# misc_sensors.net
KiCad netlist of a schematic drawn in Altium Designer
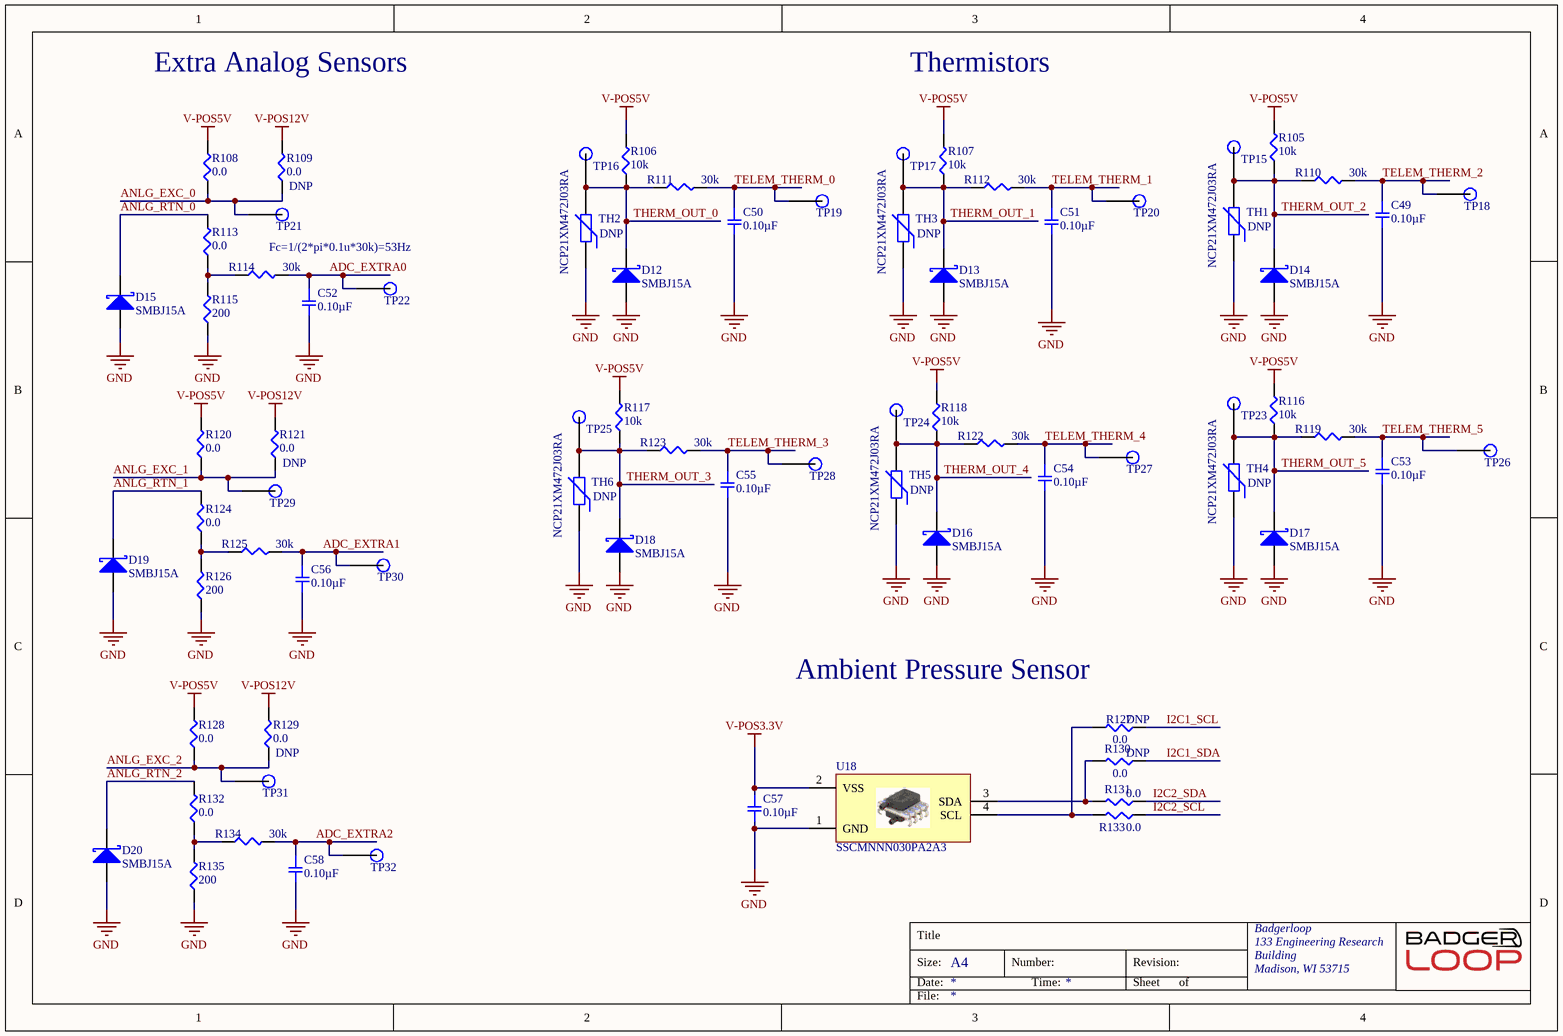
[diagram p0: misc_sensors.SchDoc]

(export (version "E")
  (design (tool "Eeschema 10.0.6"))
  (components
    (comp (ref "C49")
      (value "0.10µF")
      (footprint "SMD-0805C")
      (description "CAP CER 0.1UF 16V X7R 0805")
      (fields
        (field (name "DIGI-KEY PART NUMBER") "490-1683-1-ND")
        (field (name "PART NUMBER") "GRM219R71C104KA01D")
      )
      (libsource (lib "capacitors") (part "GRM219R71C104KA01D"))
    )
    (comp (ref "C50")
      (value "0.10µF")
      (footprint "SMD-0805C")
      (description "CAP CER 0.1UF 16V X7R 0805")
      (fields
        (field (name "DIGI-KEY PART NUMBER") "490-1683-1-ND")
        (field (name "PART NUMBER") "GRM219R71C104KA01D")
      )
      (libsource (lib "capacitors") (part "GRM219R71C104KA01D"))
    )
    (comp (ref "C51")
      (value "0.10µF")
      (footprint "SMD-0805C")
      (description "CAP CER 0.1UF 16V X7R 0805")
      (fields
        (field (name "DIGI-KEY PART NUMBER") "490-1683-1-ND")
        (field (name "PART NUMBER") "GRM219R71C104KA01D")
      )
      (libsource (lib "capacitors") (part "GRM219R71C104KA01D"))
    )
    (comp (ref "C52")
      (value "0.10µF")
      (footprint "SMD-0805C")
      (description "CAP CER 0.1UF 25V X7R 0805")
      (fields
        (field (name "DIGI-KEY PART NUMBER") "490-12754-1-ND")
        (field (name "PART NUMBER") "GRM219R71E104KA01D")
      )
      (libsource (lib "capacitors") (part "GRM219R71E104KA01D"))
    )
    (comp (ref "C53")
      (value "0.10µF")
      (footprint "SMD-0805C")
      (description "CAP CER 0.1UF 16V X7R 0805")
      (fields
        (field (name "DIGI-KEY PART NUMBER") "490-1683-1-ND")
        (field (name "PART NUMBER") "GRM219R71C104KA01D")
      )
      (libsource (lib "capacitors") (part "GRM219R71C104KA01D"))
    )
    (comp (ref "C54")
      (value "0.10µF")
      (footprint "SMD-0805C")
      (description "CAP CER 0.1UF 16V X7R 0805")
      (fields
        (field (name "DIGI-KEY PART NUMBER") "490-1683-1-ND")
        (field (name "PART NUMBER") "GRM219R71C104KA01D")
      )
      (libsource (lib "capacitors") (part "GRM219R71C104KA01D"))
    )
    (comp (ref "C55")
      (value "0.10µF")
      (footprint "SMD-0805C")
      (description "CAP CER 0.1UF 16V X7R 0805")
      (fields
        (field (name "DIGI-KEY PART NUMBER") "490-1683-1-ND")
        (field (name "PART NUMBER") "GRM219R71C104KA01D")
      )
      (libsource (lib "capacitors") (part "GRM219R71C104KA01D"))
    )
    (comp (ref "C56")
      (value "0.10µF")
      (footprint "SMD-0805C")
      (description "CAP CER 0.1UF 25V X7R 0805")
      (fields
        (field (name "DIGI-KEY PART NUMBER") "490-12754-1-ND")
        (field (name "PART NUMBER") "GRM219R71E104KA01D")
      )
      (libsource (lib "capacitors") (part "GRM219R71E104KA01D"))
    )
    (comp (ref "C57")
      (value "0.10µF")
      (footprint "SMD-0805C")
      (description "CAP CER 0.1UF 25V X7R 0805")
      (fields
        (field (name "DIGI-KEY PART NUMBER") "490-12754-1-ND")
        (field (name "PART NUMBER") "GRM219R71E104KA01D")
      )
      (libsource (lib "capacitors") (part "GRM219R71E104KA01D"))
    )
    (comp (ref "C58")
      (value "0.10µF")
      (footprint "SMD-0805C")
      (description "CAP CER 0.1UF 25V X7R 0805")
      (fields
        (field (name "DIGI-KEY PART NUMBER") "490-12754-1-ND")
        (field (name "PART NUMBER") "GRM219R71E104KA01D")
      )
      (libsource (lib "capacitors") (part "GRM219R71E104KA01D"))
    )
    (comp (ref "D12")
      (value "SMBJ15A")
      (footprint "DIOM4436X26N")
      (description "TVS DIODE 15V 24.4V DO214AA")
      (fields (field (name "MANUFACTURER") "Littelfuse") (field (name "VOLTAGE") "5V"))
      (libsource (lib "misc") (part "SMBJ15A"))
    )
    (comp (ref "D13")
      (value "SMBJ15A")
      (footprint "DIOM4436X26N")
      (description "TVS DIODE 15V 24.4V DO214AA")
      (fields (field (name "MANUFACTURER") "Littelfuse") (field (name "VOLTAGE") "5V"))
      (libsource (lib "misc") (part "SMBJ15A"))
    )
    (comp (ref "D14")
      (value "SMBJ15A")
      (footprint "DIOM4436X26N")
      (description "TVS DIODE 15V 24.4V DO214AA")
      (fields (field (name "MANUFACTURER") "Littelfuse") (field (name "VOLTAGE") "5V"))
      (libsource (lib "misc") (part "SMBJ15A"))
    )
    (comp (ref "D15")
      (value "SMBJ15A")
      (footprint "DIOM4436X26N")
      (description "TVS DIODE 15V 24.4V DO214AA")
      (fields (field (name "MANUFACTURER") "Littelfuse") (field (name "VOLTAGE") "5V"))
      (libsource (lib "misc") (part "SMBJ15A"))
    )
    (comp (ref "D16")
      (value "SMBJ15A")
      (footprint "DIOM4436X26N")
      (description "TVS DIODE 15V 24.4V DO214AA")
      (fields (field (name "MANUFACTURER") "Littelfuse") (field (name "VOLTAGE") "5V"))
      (libsource (lib "misc") (part "SMBJ15A"))
    )
    (comp (ref "D17")
      (value "SMBJ15A")
      (footprint "DIOM4436X26N")
      (description "TVS DIODE 15V 24.4V DO214AA")
      (fields (field (name "MANUFACTURER") "Littelfuse") (field (name "VOLTAGE") "5V"))
      (libsource (lib "misc") (part "SMBJ15A"))
    )
    (comp (ref "D18")
      (value "SMBJ15A")
      (footprint "DIOM4436X26N")
      (description "TVS DIODE 15V 24.4V DO214AA")
      (fields (field (name "MANUFACTURER") "Littelfuse") (field (name "VOLTAGE") "5V"))
      (libsource (lib "misc") (part "SMBJ15A"))
    )
    (comp (ref "D19")
      (value "SMBJ15A")
      (footprint "DIOM4436X26N")
      (description "TVS DIODE 15V 24.4V DO214AA")
      (fields (field (name "MANUFACTURER") "Littelfuse") (field (name "VOLTAGE") "5V"))
      (libsource (lib "misc") (part "SMBJ15A"))
    )
    (comp (ref "D20")
      (value "SMBJ15A")
      (footprint "DIOM4436X26N")
      (description "TVS DIODE 15V 24.4V DO214AA")
      (fields (field (name "MANUFACTURER") "Littelfuse") (field (name "VOLTAGE") "5V"))
      (libsource (lib "misc") (part "SMBJ15A"))
    )
    (comp (ref "R105")
      (value "10k")
      (footprint "SMD-0805-RES")
      (description "RES SMD 10K OHM 1% 1/2W 0805")
      (fields
        (field (name "PART NUMBER") "ERJ-P06F1002V")
        (field (name "DIGI-KEY PART NUMBER") "P16059CT-ND")
      )
      (libsource (lib "resistors") (part "ERJ-P06F1002V"))
    )
    (comp (ref "R106")
      (value "10k")
      (footprint "SMD-0805-RES")
      (description "RES SMD 10K OHM 1% 1/2W 0805")
      (fields
        (field (name "PART NUMBER") "ERJ-P06F1002V")
        (field (name "DIGI-KEY PART NUMBER") "P16059CT-ND")
      )
      (libsource (lib "resistors") (part "ERJ-P06F1002V"))
    )
    (comp (ref "R107")
      (value "10k")
      (footprint "SMD-0805-RES")
      (description "RES SMD 10K OHM 1% 1/2W 0805")
      (fields
        (field (name "PART NUMBER") "ERJ-P06F1002V")
        (field (name "DIGI-KEY PART NUMBER") "P16059CT-ND")
      )
      (libsource (lib "resistors") (part "ERJ-P06F1002V"))
    )
    (comp (ref "R108")
      (value "0.0")
      (footprint "SMD-0805-RES")
      (description "RES SMD 0.0 OHM JUMPER 1/8W 0805")
      (fields (field (name "PART NUMBER") "ERJ-6GEY0R00V") (field (name "DIGI-KEY PART NUMBER") "P0.0ACT-ND"))
      (libsource (lib "resistors") (part "ERJ-6GEY0R00V"))
    )
    (comp (ref "R109")
      (value "0.0")
      (footprint "SMD-0805-RES")
      (description "RES SMD 0.0 OHM JUMPER 1/8W 0805")
      (fields
        (field (name "PART NUMBER") "ERJ-6GEY0R00V")
        (field (name "DIGI-KEY PART NUMBER") "P0.0ACT-ND")
        (field (name "DNP") "DNP")
      )
      (libsource (lib "resistors") (part "ERJ-6GEY0R00V"))
    )
    (comp (ref "R110")
      (value "30k")
      (footprint "SMD-0805-RES")
      (description "RES SMD 30K OHM 1% 1/8W 0805")
      (fields
        (field (name "PART NUMBER") "ERJ-6ENF3002V")
        (field (name "DIGI-KEY PART NUMBER") "P30.0KCCT-ND")
      )
      (libsource (lib "resistors") (part "ERJ-6ENF3002V"))
    )
    (comp (ref "R111")
      (value "30k")
      (footprint "SMD-0805-RES")
      (description "RES SMD 30K OHM 1% 1/8W 0805")
      (fields
        (field (name "PART NUMBER") "ERJ-6ENF3002V")
        (field (name "DIGI-KEY PART NUMBER") "P30.0KCCT-ND")
      )
      (libsource (lib "resistors") (part "ERJ-6ENF3002V"))
    )
    (comp (ref "R112")
      (value "30k")
      (footprint "SMD-0805-RES")
      (description "RES SMD 30K OHM 1% 1/8W 0805")
      (fields
        (field (name "PART NUMBER") "ERJ-6ENF3002V")
        (field (name "DIGI-KEY PART NUMBER") "P30.0KCCT-ND")
      )
      (libsource (lib "resistors") (part "ERJ-6ENF3002V"))
    )
    (comp (ref "R113")
      (value "0.0")
      (footprint "SMD-0805-RES")
      (description "RES SMD 0.0 OHM JUMPER 1/8W 0805")
      (fields (field (name "PART NUMBER") "ERJ-6GEY0R00V") (field (name "DIGI-KEY PART NUMBER") "P0.0ACT-ND"))
      (libsource (lib "resistors") (part "ERJ-6GEY0R00V"))
    )
    (comp (ref "R114")
      (value "30k")
      (footprint "SMD-0805-RES")
      (description "RES SMD 30K OHM 1% 1/8W 0805")
      (fields
        (field (name "PART NUMBER") "ERJ-6ENF3002V")
        (field (name "DIGI-KEY PART NUMBER") "P30.0KCCT-ND")
      )
      (libsource (lib "resistors") (part "ERJ-6ENF3002V"))
    )
    (comp (ref "R115")
      (value "200")
      (footprint "SMD-0805-RES")
      (description "RES SMD 200 OHM 1% 1/2W 0805")
      (fields
        (field (name "PART NUMBER") "ERJ-P06F2000V")
        (field (name "DIGI-KEY PART NUMBER") "P16064CT-ND")
      )
      (libsource (lib "resistors") (part "ERJ-P06F2000V"))
    )
    (comp (ref "R116")
      (value "10k")
      (footprint "SMD-0805-RES")
      (description "RES SMD 10K OHM 1% 1/2W 0805")
      (fields
        (field (name "PART NUMBER") "ERJ-P06F1002V")
        (field (name "DIGI-KEY PART NUMBER") "P16059CT-ND")
      )
      (libsource (lib "resistors") (part "ERJ-P06F1002V"))
    )
    (comp (ref "R117")
      (value "10k")
      (footprint "SMD-0805-RES")
      (description "RES SMD 10K OHM 1% 1/2W 0805")
      (fields
        (field (name "PART NUMBER") "ERJ-P06F1002V")
        (field (name "DIGI-KEY PART NUMBER") "P16059CT-ND")
      )
      (libsource (lib "resistors") (part "ERJ-P06F1002V"))
    )
    (comp (ref "R118")
      (value "10k")
      (footprint "SMD-0805-RES")
      (description "RES SMD 10K OHM 1% 1/2W 0805")
      (fields
        (field (name "PART NUMBER") "ERJ-P06F1002V")
        (field (name "DIGI-KEY PART NUMBER") "P16059CT-ND")
      )
      (libsource (lib "resistors") (part "ERJ-P06F1002V"))
    )
    (comp (ref "R119")
      (value "30k")
      (footprint "SMD-0805-RES")
      (description "RES SMD 30K OHM 1% 1/8W 0805")
      (fields
        (field (name "PART NUMBER") "ERJ-6ENF3002V")
        (field (name "DIGI-KEY PART NUMBER") "P30.0KCCT-ND")
      )
      (libsource (lib "resistors") (part "ERJ-6ENF3002V"))
    )
    (comp (ref "R120")
      (value "0.0")
      (footprint "SMD-0805-RES")
      (description "RES SMD 0.0 OHM JUMPER 1/8W 0805")
      (fields (field (name "PART NUMBER") "ERJ-6GEY0R00V") (field (name "DIGI-KEY PART NUMBER") "P0.0ACT-ND"))
      (libsource (lib "resistors") (part "ERJ-6GEY0R00V"))
    )
    (comp (ref "R121")
      (value "0.0")
      (footprint "SMD-0805-RES")
      (description "RES SMD 0.0 OHM JUMPER 1/8W 0805")
      (fields
        (field (name "PART NUMBER") "ERJ-6GEY0R00V")
        (field (name "DIGI-KEY PART NUMBER") "P0.0ACT-ND")
        (field (name "DNP") "DNP")
      )
      (libsource (lib "resistors") (part "ERJ-6GEY0R00V"))
    )
    (comp (ref "R122")
      (value "30k")
      (footprint "SMD-0805-RES")
      (description "RES SMD 30K OHM 1% 1/8W 0805")
      (fields
        (field (name "PART NUMBER") "ERJ-6ENF3002V")
        (field (name "DIGI-KEY PART NUMBER") "P30.0KCCT-ND")
      )
      (libsource (lib "resistors") (part "ERJ-6ENF3002V"))
    )
    (comp (ref "R123")
      (value "30k")
      (footprint "SMD-0805-RES")
      (description "RES SMD 30K OHM 1% 1/8W 0805")
      (fields
        (field (name "PART NUMBER") "ERJ-6ENF3002V")
        (field (name "DIGI-KEY PART NUMBER") "P30.0KCCT-ND")
      )
      (libsource (lib "resistors") (part "ERJ-6ENF3002V"))
    )
    (comp (ref "R124")
      (value "0.0")
      (footprint "SMD-0805-RES")
      (description "RES SMD 0.0 OHM JUMPER 1/8W 0805")
      (fields (field (name "PART NUMBER") "ERJ-6GEY0R00V") (field (name "DIGI-KEY PART NUMBER") "P0.0ACT-ND"))
      (libsource (lib "resistors") (part "ERJ-6GEY0R00V"))
    )
    (comp (ref "R125")
      (value "30k")
      (footprint "SMD-0805-RES")
      (description "RES SMD 30K OHM 1% 1/8W 0805")
      (fields
        (field (name "PART NUMBER") "ERJ-6ENF3002V")
        (field (name "DIGI-KEY PART NUMBER") "P30.0KCCT-ND")
      )
      (libsource (lib "resistors") (part "ERJ-6ENF3002V"))
    )
    (comp (ref "R126")
      (value "200")
      (footprint "SMD-0805-RES")
      (description "RES SMD 200 OHM 1% 1/2W 0805")
      (fields
        (field (name "PART NUMBER") "ERJ-P06F2000V")
        (field (name "DIGI-KEY PART NUMBER") "P16064CT-ND")
      )
      (libsource (lib "resistors") (part "ERJ-P06F2000V"))
    )
    (comp (ref "R127")
      (value "0.0")
      (footprint "SMD-0805-RES")
      (description "RES SMD 0.0 OHM JUMPER 1/8W 0805")
      (fields
        (field (name "PART NUMBER") "ERJ-6GEY0R00V")
        (field (name "DIGI-KEY PART NUMBER") "P0.0ACT-ND")
        (field (name "DNP") "DNP")
      )
      (libsource (lib "resistors") (part "ERJ-6GEY0R00V"))
    )
    (comp (ref "R128")
      (value "0.0")
      (footprint "SMD-0805-RES")
      (description "RES SMD 0.0 OHM JUMPER 1/8W 0805")
      (fields (field (name "PART NUMBER") "ERJ-6GEY0R00V") (field (name "DIGI-KEY PART NUMBER") "P0.0ACT-ND"))
      (libsource (lib "resistors") (part "ERJ-6GEY0R00V"))
    )
    (comp (ref "R129")
      (value "0.0")
      (footprint "SMD-0805-RES")
      (description "RES SMD 0.0 OHM JUMPER 1/8W 0805")
      (fields
        (field (name "PART NUMBER") "ERJ-6GEY0R00V")
        (field (name "DIGI-KEY PART NUMBER") "P0.0ACT-ND")
        (field (name "DNP") "DNP")
      )
      (libsource (lib "resistors") (part "ERJ-6GEY0R00V"))
    )
    (comp (ref "R130")
      (value "0.0")
      (footprint "SMD-0805-RES")
      (description "RES SMD 0.0 OHM JUMPER 1/8W 0805")
      (fields
        (field (name "PART NUMBER") "ERJ-6GEY0R00V")
        (field (name "DIGI-KEY PART NUMBER") "P0.0ACT-ND")
        (field (name "DNP") "DNP")
      )
      (libsource (lib "resistors") (part "ERJ-6GEY0R00V"))
    )
    (comp (ref "R131")
      (value "0.0")
      (footprint "SMD-0805-RES")
      (description "RES SMD 0.0 OHM JUMPER 1/8W 0805")
      (fields (field (name "PART NUMBER") "ERJ-6GEY0R00V") (field (name "DIGI-KEY PART NUMBER") "P0.0ACT-ND"))
      (libsource (lib "resistors") (part "ERJ-6GEY0R00V"))
    )
    (comp (ref "R132")
      (value "0.0")
      (footprint "SMD-0805-RES")
      (description "RES SMD 0.0 OHM JUMPER 1/8W 0805")
      (fields (field (name "PART NUMBER") "ERJ-6GEY0R00V") (field (name "DIGI-KEY PART NUMBER") "P0.0ACT-ND"))
      (libsource (lib "resistors") (part "ERJ-6GEY0R00V"))
    )
    (comp (ref "R133")
      (value "0.0")
      (footprint "SMD-0805-RES")
      (description "RES SMD 0.0 OHM JUMPER 1/8W 0805")
      (fields (field (name "PART NUMBER") "ERJ-6GEY0R00V") (field (name "DIGI-KEY PART NUMBER") "P0.0ACT-ND"))
      (libsource (lib "resistors") (part "ERJ-6GEY0R00V"))
    )
    (comp (ref "R134")
      (value "30k")
      (footprint "SMD-0805-RES")
      (description "RES SMD 30K OHM 1% 1/8W 0805")
      (fields
        (field (name "PART NUMBER") "ERJ-6ENF3002V")
        (field (name "DIGI-KEY PART NUMBER") "P30.0KCCT-ND")
      )
      (libsource (lib "resistors") (part "ERJ-6ENF3002V"))
    )
    (comp (ref "R135")
      (value "200")
      (footprint "SMD-0805-RES")
      (description "RES SMD 200 OHM 1% 1/2W 0805")
      (fields
        (field (name "PART NUMBER") "ERJ-P06F2000V")
        (field (name "DIGI-KEY PART NUMBER") "P16064CT-ND")
      )
      (libsource (lib "resistors") (part "ERJ-P06F2000V"))
    )
    (comp (ref "TH1")
      (value "NCP21XM472J03RA")
      (footprint "SMD-0805-RES")
      (description "NTC THERMISTOR 4.7K OHM 5% 0805")
      (fields
        (field (name "MANUFACTURER") "Murata")
        (field (name "TOLERANCE") "5%")
        (field (name "DNP") "DNP")
      )
      (libsource (lib "misc") (part "NCP21XM472J03RA"))
    )
    (comp (ref "TH2")
      (value "NCP21XM472J03RA")
      (footprint "SMD-0805-RES")
      (description "NTC THERMISTOR 4.7K OHM 5% 0805")
      (fields
        (field (name "MANUFACTURER") "Murata")
        (field (name "TOLERANCE") "5%")
        (field (name "DNP") "DNP")
      )
      (libsource (lib "misc") (part "NCP21XM472J03RA"))
    )
    (comp (ref "TH3")
      (value "NCP21XM472J03RA")
      (footprint "SMD-0805-RES")
      (description "NTC THERMISTOR 4.7K OHM 5% 0805")
      (fields
        (field (name "MANUFACTURER") "Murata")
        (field (name "TOLERANCE") "5%")
        (field (name "DNP") "DNP")
      )
      (libsource (lib "misc") (part "NCP21XM472J03RA"))
    )
    (comp (ref "TH4")
      (value "NCP21XM472J03RA")
      (footprint "SMD-0805-RES")
      (description "NTC THERMISTOR 4.7K OHM 5% 0805")
      (fields
        (field (name "MANUFACTURER") "Murata")
        (field (name "TOLERANCE") "5%")
        (field (name "DNP") "DNP")
      )
      (libsource (lib "misc") (part "NCP21XM472J03RA"))
    )
    (comp (ref "TH5")
      (value "NCP21XM472J03RA")
      (footprint "SMD-0805-RES")
      (description "NTC THERMISTOR 4.7K OHM 5% 0805")
      (fields
        (field (name "MANUFACTURER") "Murata")
        (field (name "TOLERANCE") "5%")
        (field (name "DNP") "DNP")
      )
      (libsource (lib "misc") (part "NCP21XM472J03RA"))
    )
    (comp (ref "TH6")
      (value "NCP21XM472J03RA")
      (footprint "SMD-0805-RES")
      (description "NTC THERMISTOR 4.7K OHM 5% 0805")
      (fields
        (field (name "MANUFACTURER") "Murata")
        (field (name "TOLERANCE") "5%")
        (field (name "DNP") "DNP")
      )
      (libsource (lib "misc") (part "NCP21XM472J03RA"))
    )
    (comp (ref "TP15")
      (value "TP")
      (footprint "Test Point")
      (description "SMD TEST POINT")
      (libsource (lib "misc") (part "TP"))
    )
    (comp (ref "TP16")
      (value "TP")
      (footprint "Test Point")
      (description "SMD TEST POINT")
      (libsource (lib "misc") (part "TP"))
    )
    (comp (ref "TP17")
      (value "TP")
      (footprint "Test Point")
      (description "SMD TEST POINT")
      (libsource (lib "misc") (part "TP"))
    )
    (comp (ref "TP18")
      (value "TP")
      (footprint "Test Point")
      (description "SMD TEST POINT")
      (libsource (lib "misc") (part "TP"))
    )
    (comp (ref "TP19")
      (value "TP")
      (footprint "Test Point")
      (description "SMD TEST POINT")
      (libsource (lib "misc") (part "TP"))
    )
    (comp (ref "TP20")
      (value "TP")
      (footprint "Test Point")
      (description "SMD TEST POINT")
      (libsource (lib "misc") (part "TP"))
    )
    (comp (ref "TP21")
      (value "TP")
      (footprint "Test Point")
      (description "SMD TEST POINT")
      (libsource (lib "misc") (part "TP"))
    )
    (comp (ref "TP22")
      (value "TP")
      (footprint "Test Point")
      (description "SMD TEST POINT")
      (libsource (lib "misc") (part "TP"))
    )
    (comp (ref "TP23")
      (value "TP")
      (footprint "Test Point")
      (description "SMD TEST POINT")
      (libsource (lib "misc") (part "TP"))
    )
    (comp (ref "TP24")
      (value "TP")
      (footprint "Test Point")
      (description "SMD TEST POINT")
      (libsource (lib "misc") (part "TP"))
    )
    (comp (ref "TP25")
      (value "TP")
      (footprint "Test Point")
      (description "SMD TEST POINT")
      (libsource (lib "misc") (part "TP"))
    )
    (comp (ref "TP26")
      (value "TP")
      (footprint "Test Point")
      (description "SMD TEST POINT")
      (libsource (lib "misc") (part "TP"))
    )
    (comp (ref "TP27")
      (value "TP")
      (footprint "Test Point")
      (description "SMD TEST POINT")
      (libsource (lib "misc") (part "TP"))
    )
    (comp (ref "TP28")
      (value "TP")
      (footprint "Test Point")
      (description "SMD TEST POINT")
      (libsource (lib "misc") (part "TP"))
    )
    (comp (ref "TP29")
      (value "TP")
      (footprint "Test Point")
      (description "SMD TEST POINT")
      (libsource (lib "misc") (part "TP"))
    )
    (comp (ref "TP30")
      (value "TP")
      (footprint "Test Point")
      (description "SMD TEST POINT")
      (libsource (lib "misc") (part "TP"))
    )
    (comp (ref "TP31")
      (value "TP")
      (footprint "Test Point")
      (description "SMD TEST POINT")
      (libsource (lib "misc") (part "TP"))
    )
    (comp (ref "TP32")
      (value "TP")
      (footprint "Test Point")
      (description "SMD TEST POINT")
      (libsource (lib "misc") (part "TP"))
    )
    (comp (ref "U18")
      (value "SSCMNNN030PA2A3")
      (footprint "8-SMT")
      (description "Honeywell Digital Pressure Sensor")
      (libsource (lib "ic") (part "SSCMNNN030PA2A3"))
    )
  )
  (nets
    (net (code "1") (name "/ADC_EXTRA0") (class "Default")
      (node (ref "C52") (pin "1") (pinfunction "1_1") (pintype "passive"))
      (node (ref "R114") (pin "2") (pinfunction "2_2") (pintype "passive"))
      (node (ref "TP22") (pin "1") (pinfunction "1_1") (pintype "passive"))
    )
    (net (code "2") (name "/ADC_EXTRA1") (class "Default")
      (node (ref "C56") (pin "1") (pinfunction "1_1") (pintype "passive"))
      (node (ref "R125") (pin "2") (pinfunction "2_2") (pintype "passive"))
      (node (ref "TP30") (pin "1") (pinfunction "1_1") (pintype "passive"))
    )
    (net (code "3") (name "/ADC_EXTRA2") (class "Default")
      (node (ref "C58") (pin "1") (pinfunction "1_1") (pintype "passive"))
      (node (ref "R134") (pin "2") (pinfunction "2_2") (pintype "passive"))
      (node (ref "TP32") (pin "1") (pinfunction "1_1") (pintype "passive"))
    )
    (net (code "4") (name "/ANLG_EXC_0") (class "Default")
      (node (ref "R108") (pin "1") (pinfunction "1_1") (pintype "passive"))
      (node (ref "R109") (pin "1") (pinfunction "1_1") (pintype "passive"))
      (node (ref "TP21") (pin "1") (pinfunction "1_1") (pintype "passive"))
    )
    (net (code "5") (name "/ANLG_EXC_1") (class "Default")
      (node (ref "R120") (pin "1") (pinfunction "1_1") (pintype "passive"))
      (node (ref "R121") (pin "1") (pinfunction "1_1") (pintype "passive"))
      (node (ref "TP29") (pin "1") (pinfunction "1_1") (pintype "passive"))
    )
    (net (code "6") (name "/ANLG_EXC_2") (class "Default")
      (node (ref "R128") (pin "1") (pinfunction "1_1") (pintype "passive"))
      (node (ref "R129") (pin "1") (pinfunction "1_1") (pintype "passive"))
      (node (ref "TP31") (pin "1") (pinfunction "1_1") (pintype "passive"))
    )
    (net (code "7") (name "/ANLG_RTN_0") (class "Default")
      (node (ref "D15") (pin "1") (pinfunction "A_1") (pintype "passive"))
      (node (ref "R113") (pin "2") (pinfunction "2_2") (pintype "passive"))
    )
    (net (code "8") (name "/ANLG_RTN_1") (class "Default")
      (node (ref "D19") (pin "1") (pinfunction "A_1") (pintype "passive"))
      (node (ref "R124") (pin "2") (pinfunction "2_2") (pintype "passive"))
    )
    (net (code "9") (name "/ANLG_RTN_2") (class "Default")
      (node (ref "D20") (pin "1") (pinfunction "A_1") (pintype "passive"))
      (node (ref "R132") (pin "2") (pinfunction "2_2") (pintype "passive"))
    )
    (net (code "10") (name "/I2C1_SCL") (class "Default")
      (node (ref "R127") (pin "1") (pinfunction "1_1") (pintype "passive"))
    )
    (net (code "11") (name "/I2C1_SDA") (class "Default")
      (node (ref "R130") (pin "1") (pinfunction "1_1") (pintype "passive"))
    )
    (net (code "12") (name "/I2C2_SCL") (class "Default")
      (node (ref "R133") (pin "1") (pinfunction "1_1") (pintype "passive"))
    )
    (net (code "13") (name "/I2C2_SDA") (class "Default")
      (node (ref "R131") (pin "1") (pinfunction "1_1") (pintype "passive"))
    )
    (net (code "14") (name "/TELEM_THERM_0") (class "Default")
      (node (ref "C50") (pin "1") (pinfunction "1_1") (pintype "passive"))
      (node (ref "R111") (pin "2") (pinfunction "2_2") (pintype "passive"))
      (node (ref "TP19") (pin "1") (pinfunction "1_1") (pintype "passive"))
    )
    (net (code "15") (name "/TELEM_THERM_1") (class "Default")
      (node (ref "C51") (pin "1") (pinfunction "1_1") (pintype "passive"))
      (node (ref "R112") (pin "2") (pinfunction "2_2") (pintype "passive"))
      (node (ref "TP20") (pin "1") (pinfunction "1_1") (pintype "passive"))
    )
    (net (code "16") (name "/TELEM_THERM_2") (class "Default")
      (node (ref "C49") (pin "1") (pinfunction "1_1") (pintype "passive"))
      (node (ref "R110") (pin "2") (pinfunction "2_2") (pintype "passive"))
      (node (ref "TP18") (pin "1") (pinfunction "1_1") (pintype "passive"))
    )
    (net (code "17") (name "/TELEM_THERM_3") (class "Default")
      (node (ref "C55") (pin "1") (pinfunction "1_1") (pintype "passive"))
      (node (ref "R123") (pin "2") (pinfunction "2_2") (pintype "passive"))
      (node (ref "TP28") (pin "1") (pinfunction "1_1") (pintype "passive"))
    )
    (net (code "18") (name "/TELEM_THERM_4") (class "Default")
      (node (ref "C54") (pin "1") (pinfunction "1_1") (pintype "passive"))
      (node (ref "R122") (pin "2") (pinfunction "2_2") (pintype "passive"))
      (node (ref "TP27") (pin "1") (pinfunction "1_1") (pintype "passive"))
    )
    (net (code "19") (name "/TELEM_THERM_5") (class "Default")
      (node (ref "C53") (pin "1") (pinfunction "1_1") (pintype "passive"))
      (node (ref "R119") (pin "2") (pinfunction "2_2") (pintype "passive"))
      (node (ref "TP26") (pin "1") (pinfunction "1_1") (pintype "passive"))
    )
    (net (code "20") (name "/THERM_OUT_0") (class "Default")
      (node (ref "D12") (pin "1") (pinfunction "A_1") (pintype "passive"))
      (node (ref "R106") (pin "1") (pinfunction "1_1") (pintype "passive"))
      (node (ref "R111") (pin "1") (pinfunction "1_1") (pintype "passive"))
      (node (ref "TH2") (pin "2") (pinfunction "2_2") (pintype "passive"))
      (node (ref "TP16") (pin "1") (pinfunction "1_1") (pintype "passive"))
    )
    (net (code "21") (name "/THERM_OUT_1") (class "Default")
      (node (ref "D13") (pin "1") (pinfunction "A_1") (pintype "passive"))
      (node (ref "R107") (pin "1") (pinfunction "1_1") (pintype "passive"))
      (node (ref "R112") (pin "1") (pinfunction "1_1") (pintype "passive"))
      (node (ref "TH3") (pin "2") (pinfunction "2_2") (pintype "passive"))
      (node (ref "TP17") (pin "1") (pinfunction "1_1") (pintype "passive"))
    )
    (net (code "22") (name "/THERM_OUT_2") (class "Default")
      (node (ref "D14") (pin "1") (pinfunction "A_1") (pintype "passive"))
      (node (ref "R105") (pin "1") (pinfunction "1_1") (pintype "passive"))
      (node (ref "R110") (pin "1") (pinfunction "1_1") (pintype "passive"))
      (node (ref "TH1") (pin "2") (pinfunction "2_2") (pintype "passive"))
      (node (ref "TP15") (pin "1") (pinfunction "1_1") (pintype "passive"))
    )
    (net (code "23") (name "/THERM_OUT_3") (class "Default")
      (node (ref "D18") (pin "1") (pinfunction "A_1") (pintype "passive"))
      (node (ref "R117") (pin "1") (pinfunction "1_1") (pintype "passive"))
      (node (ref "R123") (pin "1") (pinfunction "1_1") (pintype "passive"))
      (node (ref "TH6") (pin "2") (pinfunction "2_2") (pintype "passive"))
      (node (ref "TP25") (pin "1") (pinfunction "1_1") (pintype "passive"))
    )
    (net (code "24") (name "/THERM_OUT_4") (class "Default")
      (node (ref "D16") (pin "1") (pinfunction "A_1") (pintype "passive"))
      (node (ref "R118") (pin "1") (pinfunction "1_1") (pintype "passive"))
      (node (ref "R122") (pin "1") (pinfunction "1_1") (pintype "passive"))
      (node (ref "TH5") (pin "2") (pinfunction "2_2") (pintype "passive"))
      (node (ref "TP24") (pin "1") (pinfunction "1_1") (pintype "passive"))
    )
    (net (code "25") (name "/THERM_OUT_5") (class "Default")
      (node (ref "D17") (pin "1") (pinfunction "A_1") (pintype "passive"))
      (node (ref "R116") (pin "1") (pinfunction "1_1") (pintype "passive"))
      (node (ref "R119") (pin "1") (pinfunction "1_1") (pintype "passive"))
      (node (ref "TH4") (pin "2") (pinfunction "2_2") (pintype "passive"))
      (node (ref "TP23") (pin "1") (pinfunction "1_1") (pintype "passive"))
    )
    (net (code "26") (name "GND") (class "Default")
      (node (ref "C49") (pin "2") (pinfunction "2_2") (pintype "passive"))
      (node (ref "C50") (pin "2") (pinfunction "2_2") (pintype "passive"))
      (node (ref "C51") (pin "2") (pinfunction "2_2") (pintype "passive"))
      (node (ref "C52") (pin "2") (pinfunction "2_2") (pintype "passive"))
      (node (ref "C53") (pin "2") (pinfunction "2_2") (pintype "passive"))
      (node (ref "C54") (pin "2") (pinfunction "2_2") (pintype "passive"))
      (node (ref "C55") (pin "2") (pinfunction "2_2") (pintype "passive"))
      (node (ref "C56") (pin "2") (pinfunction "2_2") (pintype "passive"))
      (node (ref "C57") (pin "2") (pinfunction "2_2") (pintype "passive"))
      (node (ref "C58") (pin "2") (pinfunction "2_2") (pintype "passive"))
      (node (ref "D12") (pin "2") (pinfunction "K_2") (pintype "passive"))
      (node (ref "D13") (pin "2") (pinfunction "K_2") (pintype "passive"))
      (node (ref "D14") (pin "2") (pinfunction "K_2") (pintype "passive"))
      (node (ref "D15") (pin "2") (pinfunction "K_2") (pintype "passive"))
      (node (ref "D16") (pin "2") (pinfunction "K_2") (pintype "passive"))
      (node (ref "D17") (pin "2") (pinfunction "K_2") (pintype "passive"))
      (node (ref "D18") (pin "2") (pinfunction "K_2") (pintype "passive"))
      (node (ref "D19") (pin "2") (pinfunction "K_2") (pintype "passive"))
      (node (ref "D20") (pin "2") (pinfunction "K_2") (pintype "passive"))
      (node (ref "R115") (pin "1") (pinfunction "1_1") (pintype "passive"))
      (node (ref "R126") (pin "1") (pinfunction "1_1") (pintype "passive"))
      (node (ref "R135") (pin "1") (pinfunction "1_1") (pintype "passive"))
      (node (ref "TH1") (pin "1") (pinfunction "1_1") (pintype "passive"))
      (node (ref "TH2") (pin "1") (pinfunction "1_1") (pintype "passive"))
      (node (ref "TH3") (pin "1") (pinfunction "1_1") (pintype "passive"))
      (node (ref "TH4") (pin "1") (pinfunction "1_1") (pintype "passive"))
      (node (ref "TH5") (pin "1") (pinfunction "1_1") (pintype "passive"))
      (node (ref "TH6") (pin "1") (pinfunction "1_1") (pintype "passive"))
      (node (ref "U18") (pin "1") (pinfunction "GND_1") (pintype "power_in"))
    )
    (net (code "27") (name "Net-(R113-Pad1)") (class "Default")
      (node (ref "R113") (pin "1") (pinfunction "1_1") (pintype "passive"))
      (node (ref "R114") (pin "1") (pinfunction "1_1") (pintype "passive"))
      (node (ref "R115") (pin "2") (pinfunction "2_2") (pintype "passive"))
    )
    (net (code "28") (name "Net-(R124-Pad1)") (class "Default")
      (node (ref "R124") (pin "1") (pinfunction "1_1") (pintype "passive"))
      (node (ref "R125") (pin "1") (pinfunction "1_1") (pintype "passive"))
      (node (ref "R126") (pin "2") (pinfunction "2_2") (pintype "passive"))
    )
    (net (code "29") (name "Net-(R132-Pad1)") (class "Default")
      (node (ref "R132") (pin "1") (pinfunction "1_1") (pintype "passive"))
      (node (ref "R134") (pin "1") (pinfunction "1_1") (pintype "passive"))
      (node (ref "R135") (pin "2") (pinfunction "2_2") (pintype "passive"))
    )
    (net (code "30") (name "Net-(U18-SCL)") (class "Default")
      (node (ref "R127") (pin "2") (pinfunction "2_2") (pintype "passive"))
      (node (ref "R133") (pin "2") (pinfunction "2_2") (pintype "passive"))
      (node (ref "U18") (pin "4") (pinfunction "SCL_4") (pintype "passive"))
    )
    (net (code "31") (name "Net-(U18-SDA)") (class "Default")
      (node (ref "R130") (pin "2") (pinfunction "2_2") (pintype "passive"))
      (node (ref "R131") (pin "2") (pinfunction "2_2") (pintype "passive"))
      (node (ref "U18") (pin "3") (pinfunction "SDA_3") (pintype "passive"))
    )
    (net (code "32") (name "V-POS3.3V") (class "Default")
      (node (ref "C57") (pin "1") (pinfunction "1_1") (pintype "passive"))
      (node (ref "U18") (pin "2") (pinfunction "VSS_2") (pintype "power_in"))
    )
    (net (code "33") (name "V-POS5V") (class "Default")
      (node (ref "R105") (pin "2") (pinfunction "2_2") (pintype "passive"))
      (node (ref "R106") (pin "2") (pinfunction "2_2") (pintype "passive"))
      (node (ref "R107") (pin "2") (pinfunction "2_2") (pintype "passive"))
      (node (ref "R108") (pin "2") (pinfunction "2_2") (pintype "passive"))
      (node (ref "R116") (pin "2") (pinfunction "2_2") (pintype "passive"))
      (node (ref "R117") (pin "2") (pinfunction "2_2") (pintype "passive"))
      (node (ref "R118") (pin "2") (pinfunction "2_2") (pintype "passive"))
      (node (ref "R120") (pin "2") (pinfunction "2_2") (pintype "passive"))
      (node (ref "R128") (pin "2") (pinfunction "2_2") (pintype "passive"))
    )
    (net (code "34") (name "V-POS12V") (class "Default")
      (node (ref "R109") (pin "2") (pinfunction "2_2") (pintype "passive"))
      (node (ref "R121") (pin "2") (pinfunction "2_2") (pintype "passive"))
      (node (ref "R129") (pin "2") (pinfunction "2_2") (pintype "passive"))
    )
  )
)
